# TL1P4.net
KiCad netlist of a schematic drawn in EAGLE
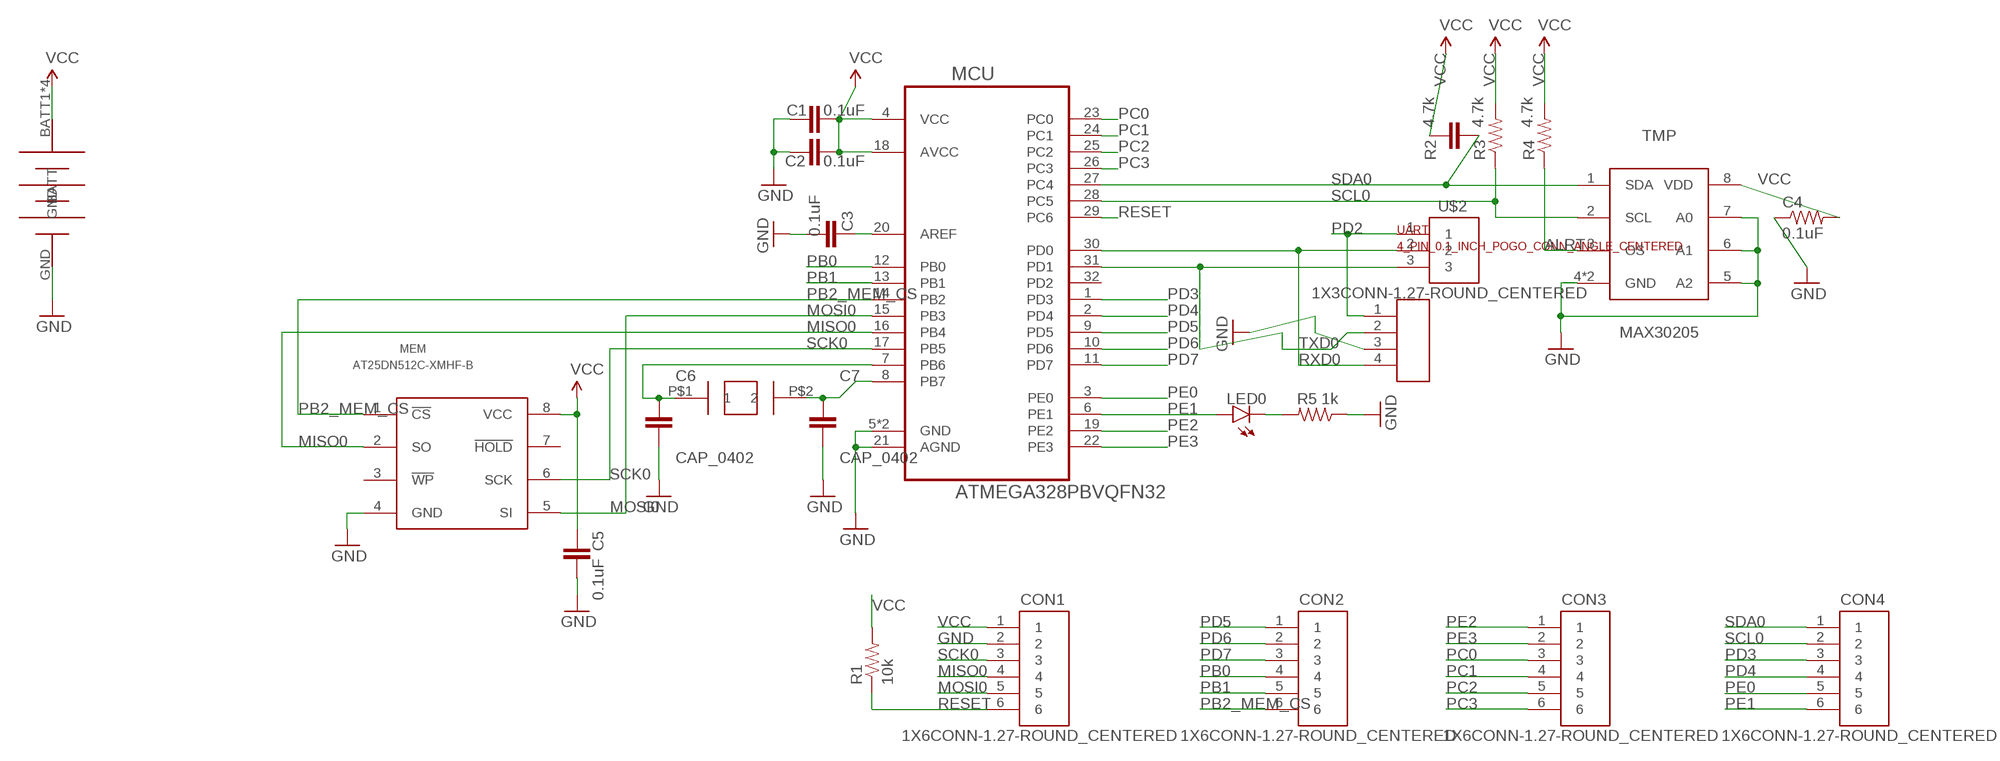
[diagram p0: schematic, sheet 1]

(export (version "E")
  (design (tool "Eeschema 10.0.6"))
  (components
    (comp (ref "C1")
      (value "0.1uF")
      (footprint "eagle-import:RES_CAP_0201")
      (libsource (lib "eagle-import") (part "CAP_0201_CERAMIC"))
    )
    (comp (ref "C2")
      (value "0.1uF")
      (footprint "eagle-import:RES_CAP_0201")
      (libsource (lib "eagle-import") (part "CAP_0201_CERAMIC"))
    )
    (comp (ref "C3")
      (value "0.1uF")
      (footprint "eagle-import:RES_CAP_0201")
      (libsource (lib "eagle-import") (part "CAP_0201_CERAMIC"))
    )
    (comp (ref "C4")
      (value "0.1uF")
      (footprint "eagle-import:RES_CAP_0201")
      (libsource (lib "eagle-import") (part "RES_0201_CERAMIC"))
    )
    (comp (ref "C5")
      (value "0.1uF")
      (footprint "eagle-import:RES_CAP_0201")
      (libsource (lib "eagle-import") (part "CAP_0201_CERAMIC"))
    )
    (comp (ref "C6")
      (value "CAP_0402")
      (footprint "eagle-import:SMD_0402")
      (libsource (lib "eagle-import") (part "CAP_0402"))
    )
    (comp (ref "C7")
      (value "CAP_0402")
      (footprint "eagle-import:SMD_0402")
      (libsource (lib "eagle-import") (part "CAP_0402"))
    )
    (comp (ref "CON1")
      (value "1X6CONN-1.27-ROUND_CENTERED")
      (footprint "eagle-import:1X6_1.27_ROUND_CENTERED")
      (libsource (lib "eagle-import") (part "1X6CONN-1.27-ROUND_CENTERED"))
    )
    (comp (ref "CON2")
      (value "1X6CONN-1.27-ROUND_CENTERED")
      (footprint "eagle-import:1X6_1.27_ROUND_CENTERED")
      (libsource (lib "eagle-import") (part "1X6CONN-1.27-ROUND_CENTERED"))
    )
    (comp (ref "CON3")
      (value "1X6CONN-1.27-ROUND_CENTERED")
      (footprint "eagle-import:1X6_1.27_ROUND_CENTERED")
      (libsource (lib "eagle-import") (part "1X6CONN-1.27-ROUND_CENTERED"))
    )
    (comp (ref "CON4")
      (value "1X6CONN-1.27-ROUND_CENTERED")
      (footprint "eagle-import:1X6_1.27_ROUND_CENTERED")
      (libsource (lib "eagle-import") (part "1X6CONN-1.27-ROUND_CENTERED"))
    )
    (comp (ref "LED0")
      (value "LED_0402")
      (footprint "eagle-import:LED_0402")
      (libsource (lib "eagle-import") (part "LED_0402"))
    )
    (comp (ref "MCU")
      (value "ATMEGA328PBVQFN32")
      (footprint "eagle-import:ATMEGA328PB_VFQFN32")
      (libsource (lib "eagle-import") (part "ATMEGA328PBVQFN32"))
    )
    (comp (ref "MEM")
      (value "AT25DN512C-XMHF-B")
      (footprint "eagle-import:TSSSOP-8")
      (libsource (lib "eagle-import") (part "AT25DN512C-XMHF-B"))
    )
    (comp (ref "R1")
      (value "10k")
      (footprint "eagle-import:RES_CAP_0201")
      (libsource (lib "eagle-import") (part "RES_0201_CERAMIC"))
    )
    (comp (ref "R2")
      (value "4.7k")
      (footprint "eagle-import:RES_CAP_0201")
      (libsource (lib "eagle-import") (part "CAP_0201_CERAMIC"))
    )
    (comp (ref "R3")
      (value "4.7k")
      (footprint "eagle-import:RES_CAP_0201")
      (libsource (lib "eagle-import") (part "RES_0201_CERAMIC"))
    )
    (comp (ref "R4")
      (value "4.7k")
      (footprint "eagle-import:RES_CAP_0201")
      (libsource (lib "eagle-import") (part "RES_0201_CERAMIC"))
    )
    (comp (ref "R5")
      (value "1k")
      (footprint "eagle-import:RES_CAP_0201")
      (libsource (lib "eagle-import") (part "RES_0201_CERAMIC"))
    )
    (comp (ref "T1")
      (value "ABS07AIG")
      (footprint "eagle-import:ABS07AIG")
      (libsource (lib "eagle-import") (part "ABS07AIG"))
    )
    (comp (ref "TMP")
      (value "MAX30205")
      (footprint "eagle-import:MAX30205_TDFN8")
      (libsource (lib "eagle-import") (part "MAX30205"))
    )
    (comp (ref "U$1")
      (value "LINX-CR2032-BAT-HLD-THM")
      (footprint "eagle-import:CR2032-LINX-THM")
      (libsource (lib "eagle-import") (part "LINX-CR2032-BAT-HLD-THM"))
    )
    (comp (ref "U$2")
      (value "1X3CONN-1.27-ROUND_CENTERED")
      (footprint "eagle-import:1X3_1.27_ROUND_CENTERED")
      (libsource (lib "eagle-import") (part "1X3CONN-1.27-ROUND_CENTERED"))
    )
    (comp (ref "UART")
      (value "4_PIN_0.1_INCH_POGO_CONN_ANGLE_CENTERED")
      (footprint "eagle-import:4_PIN_0.1__POGO_ANGLE_CENTERED")
      (libsource (lib "eagle-import") (part "4_PIN_0.1_INCH_POGO_CONN_ANGLE_CENTERED"))
    )
  )
  (nets
    (net (code "1") (name "/ALRT") (class "Default")
      (node (ref "R4") (pin "2") (pinfunction "2_2") (pintype "passive"))
      (node (ref "TMP") (pin "3") (pinfunction "OS_3") (pintype "bidirectional"))
    )
    (net (code "2") (name "/MISO0") (class "Default")
      (node (ref "CON1") (pin "4") (pinfunction "4_4") (pintype "bidirectional"))
      (node (ref "MCU") (pin "16") (pinfunction "PB4_16") (pintype "bidirectional"))
      (node (ref "MEM") (pin "2") (pinfunction "SO_2") (pintype "bidirectional"))
    )
    (net (code "3") (name "/MOSI0") (class "Default")
      (node (ref "CON1") (pin "5") (pinfunction "5_5") (pintype "bidirectional"))
      (node (ref "MCU") (pin "15") (pinfunction "PB3_15") (pintype "bidirectional"))
      (node (ref "MEM") (pin "5") (pinfunction "SI_5") (pintype "bidirectional"))
    )
    (net (code "4") (name "/PB0") (class "Default")
      (node (ref "CON2") (pin "4") (pinfunction "4_4") (pintype "bidirectional"))
      (node (ref "MCU") (pin "12") (pinfunction "PB0_12") (pintype "bidirectional"))
    )
    (net (code "5") (name "/PB1") (class "Default")
      (node (ref "CON2") (pin "5") (pinfunction "5_5") (pintype "bidirectional"))
      (node (ref "MCU") (pin "13") (pinfunction "PB1_13") (pintype "bidirectional"))
    )
    (net (code "6") (name "/PB2_MEM_CS") (class "Default")
      (node (ref "CON2") (pin "6") (pinfunction "6_6") (pintype "bidirectional"))
      (node (ref "MCU") (pin "14") (pinfunction "PB2_14") (pintype "bidirectional"))
      (node (ref "MEM") (pin "1") (pinfunction "~{CS}_1") (pintype "bidirectional"))
    )
    (net (code "7") (name "/PC0") (class "Default")
      (node (ref "CON3") (pin "3") (pinfunction "3_3") (pintype "bidirectional"))
      (node (ref "MCU") (pin "23") (pinfunction "PC0_23") (pintype "bidirectional"))
    )
    (net (code "8") (name "/PC1") (class "Default")
      (node (ref "CON3") (pin "4") (pinfunction "4_4") (pintype "bidirectional"))
      (node (ref "MCU") (pin "24") (pinfunction "PC1_24") (pintype "bidirectional"))
    )
    (net (code "9") (name "/PC2") (class "Default")
      (node (ref "CON3") (pin "5") (pinfunction "5_5") (pintype "bidirectional"))
      (node (ref "MCU") (pin "25") (pinfunction "PC2_25") (pintype "bidirectional"))
    )
    (net (code "10") (name "/PC3") (class "Default")
      (node (ref "CON3") (pin "6") (pinfunction "6_6") (pintype "bidirectional"))
      (node (ref "MCU") (pin "26") (pinfunction "PC3_26") (pintype "bidirectional"))
    )
    (net (code "11") (name "/PD2") (class "Default")
      (node (ref "U$2") (pin "1") (pinfunction "1_1") (pintype "bidirectional"))
      (node (ref "UART") (pin "1") (pinfunction "1_1") (pintype "bidirectional"))
    )
    (net (code "12") (name "/PD3") (class "Default")
      (node (ref "CON4") (pin "3") (pinfunction "3_3") (pintype "bidirectional"))
      (node (ref "MCU") (pin "1") (pinfunction "PD3_1") (pintype "bidirectional"))
    )
    (net (code "13") (name "/PD4") (class "Default")
      (node (ref "CON4") (pin "4") (pinfunction "4_4") (pintype "bidirectional"))
      (node (ref "MCU") (pin "2") (pinfunction "PD4_2") (pintype "bidirectional"))
    )
    (net (code "14") (name "/PD5") (class "Default")
      (node (ref "CON2") (pin "1") (pinfunction "1_1") (pintype "bidirectional"))
      (node (ref "MCU") (pin "9") (pinfunction "PD5_9") (pintype "bidirectional"))
    )
    (net (code "15") (name "/PD6") (class "Default")
      (node (ref "CON2") (pin "2") (pinfunction "2_2") (pintype "bidirectional"))
      (node (ref "MCU") (pin "10") (pinfunction "PD6_10") (pintype "bidirectional"))
    )
    (net (code "16") (name "/PD7") (class "Default")
      (node (ref "CON2") (pin "3") (pinfunction "3_3") (pintype "bidirectional"))
      (node (ref "MCU") (pin "11") (pinfunction "PD7_11") (pintype "bidirectional"))
    )
    (net (code "17") (name "/PE0") (class "Default")
      (node (ref "CON4") (pin "5") (pinfunction "5_5") (pintype "bidirectional"))
      (node (ref "MCU") (pin "3") (pinfunction "PE0_3") (pintype "bidirectional"))
    )
    (net (code "18") (name "/PE1") (class "Default")
      (node (ref "CON4") (pin "6") (pinfunction "6_6") (pintype "bidirectional"))
      (node (ref "LED0") (pin "ANODE") (pinfunction "A_ANODE") (pintype "passive"))
      (node (ref "MCU") (pin "6") (pinfunction "PE1_6") (pintype "bidirectional"))
    )
    (net (code "19") (name "/PE2") (class "Default")
      (node (ref "CON3") (pin "1") (pinfunction "1_1") (pintype "bidirectional"))
      (node (ref "MCU") (pin "19") (pinfunction "PE2_19") (pintype "bidirectional"))
    )
    (net (code "20") (name "/PE3") (class "Default")
      (node (ref "CON3") (pin "2") (pinfunction "2_2") (pintype "bidirectional"))
      (node (ref "MCU") (pin "22") (pinfunction "PE3_22") (pintype "bidirectional"))
    )
    (net (code "21") (name "/RESET") (class "Default")
      (node (ref "CON1") (pin "6") (pinfunction "6_6") (pintype "bidirectional"))
      (node (ref "MCU") (pin "29") (pinfunction "PC6_29") (pintype "bidirectional"))
      (node (ref "R1") (pin "2") (pinfunction "2_2") (pintype "passive"))
    )
    (net (code "22") (name "/RXD0") (class "Default")
      (node (ref "MCU") (pin "30") (pinfunction "PD0_30") (pintype "bidirectional"))
      (node (ref "U$2") (pin "2") (pinfunction "2_2") (pintype "bidirectional"))
      (node (ref "UART") (pin "4") (pinfunction "4_4") (pintype "bidirectional"))
    )
    (net (code "23") (name "/SCK0") (class "Default")
      (node (ref "CON1") (pin "3") (pinfunction "3_3") (pintype "bidirectional"))
      (node (ref "MCU") (pin "17") (pinfunction "PB5_17") (pintype "bidirectional"))
      (node (ref "MEM") (pin "6") (pinfunction "SCK_6") (pintype "bidirectional"))
    )
    (net (code "24") (name "/SCL0") (class "Default")
      (node (ref "CON4") (pin "2") (pinfunction "2_2") (pintype "bidirectional"))
      (node (ref "MCU") (pin "28") (pinfunction "PC5_28") (pintype "bidirectional"))
      (node (ref "R3") (pin "2") (pinfunction "2_2") (pintype "passive"))
      (node (ref "TMP") (pin "2") (pinfunction "SCL_2") (pintype "bidirectional"))
    )
    (net (code "25") (name "/SDA0") (class "Default")
      (node (ref "CON4") (pin "1") (pinfunction "1_1") (pintype "bidirectional"))
      (node (ref "MCU") (pin "27") (pinfunction "PC4_27") (pintype "bidirectional"))
      (node (ref "R2") (pin "2") (pinfunction "2_2") (pintype "passive"))
      (node (ref "TMP") (pin "1") (pinfunction "SDA_1") (pintype "bidirectional"))
    )
    (net (code "26") (name "/TXD0") (class "Default")
      (node (ref "MCU") (pin "31") (pinfunction "PD1_31") (pintype "bidirectional"))
      (node (ref "U$2") (pin "3") (pinfunction "3_3") (pintype "bidirectional"))
      (node (ref "UART") (pin "2") (pinfunction "2_2") (pintype "bidirectional"))
    )
    (net (code "27") (name "GND") (class "Default")
      (node (ref "C1") (pin "2") (pinfunction "2_2") (pintype "passive"))
      (node (ref "C2") (pin "2") (pinfunction "2_2") (pintype "passive"))
      (node (ref "C3") (pin "2") (pinfunction "2_2") (pintype "passive"))
      (node (ref "C4") (pin "2") (pinfunction "2_2") (pintype "passive"))
      (node (ref "C5") (pin "2") (pinfunction "2_2") (pintype "passive"))
      (node (ref "C6") (pin "2") (pinfunction "2_2") (pintype "bidirectional"))
      (node (ref "C7") (pin "2") (pinfunction "2_2") (pintype "bidirectional"))
      (node (ref "CON1") (pin "2") (pinfunction "2_2") (pintype "bidirectional"))
      (node (ref "MCU") (pin "21") (pinfunction "AGND_21") (pintype "passive"))
      (node (ref "MCU") (pin "5") (pinfunction "GND_5") (pintype "passive"))
      (node (ref "MCU") (pin "PAD") (pinfunction "GND_PAD") (pintype "passive"))
      (node (ref "MEM") (pin "4") (pinfunction "GND_4") (pintype "bidirectional"))
      (node (ref "R5") (pin "2") (pinfunction "2_2") (pintype "passive"))
      (node (ref "TMP") (pin "4") (pinfunction "GND_4") (pintype "bidirectional"))
      (node (ref "TMP") (pin "5") (pinfunction "A2_5") (pintype "bidirectional"))
      (node (ref "TMP") (pin "6") (pinfunction "A1_6") (pintype "bidirectional"))
      (node (ref "TMP") (pin "7") (pinfunction "A0_7") (pintype "bidirectional"))
      (node (ref "TMP") (pin "PAD") (pinfunction "GND_PAD") (pintype "bidirectional"))
      (node (ref "U$1") (pin "GND") (pinfunction "GND_GND") (pintype "bidirectional"))
      (node (ref "UART") (pin "3") (pinfunction "3_3") (pintype "bidirectional"))
    )
    (net (code "28") (name "Net-(LED0-C)") (class "Default")
      (node (ref "LED0") (pin "CATHODE") (pinfunction "C_CATHODE") (pintype "passive"))
      (node (ref "R5") (pin "1") (pinfunction "1_1") (pintype "passive"))
    )
    (net (code "29") (name "Net-(MCU-AREF)") (class "Default")
      (node (ref "C3") (pin "1") (pinfunction "1_1") (pintype "passive"))
      (node (ref "MCU") (pin "20") (pinfunction "AREF_20") (pintype "input"))
    )
    (net (code "30") (name "Net-(MCU-PB6)") (class "Default")
      (node (ref "C6") (pin "1") (pinfunction "1_1") (pintype "bidirectional"))
      (node (ref "MCU") (pin "7") (pinfunction "PB6_7") (pintype "bidirectional"))
      (node (ref "T1") (pin "P$1") (pinfunction "1_P$1") (pintype "bidirectional"))
    )
    (net (code "31") (name "Net-(MCU-PB7)") (class "Default")
      (node (ref "C7") (pin "1") (pinfunction "1_1") (pintype "bidirectional"))
      (node (ref "MCU") (pin "8") (pinfunction "PB7_8") (pintype "bidirectional"))
      (node (ref "T1") (pin "P$2") (pinfunction "2_P$2") (pintype "bidirectional"))
    )
    (net (code "32") (name "VCC") (class "Default")
      (node (ref "C1") (pin "1") (pinfunction "1_1") (pintype "passive"))
      (node (ref "C2") (pin "1") (pinfunction "1_1") (pintype "passive"))
      (node (ref "C4") (pin "1") (pinfunction "1_1") (pintype "passive"))
      (node (ref "C5") (pin "1") (pinfunction "1_1") (pintype "passive"))
      (node (ref "CON1") (pin "1") (pinfunction "1_1") (pintype "bidirectional"))
      (node (ref "MCU") (pin "18") (pinfunction "AVCC_18") (pintype "power_in"))
      (node (ref "MCU") (pin "4") (pinfunction "VCC_4") (pintype "power_in"))
      (node (ref "MEM") (pin "8") (pinfunction "VCC_8") (pintype "bidirectional"))
      (node (ref "R1") (pin "1") (pinfunction "1_1") (pintype "passive"))
      (node (ref "R2") (pin "1") (pinfunction "1_1") (pintype "passive"))
      (node (ref "R3") (pin "1") (pinfunction "1_1") (pintype "passive"))
      (node (ref "R4") (pin "1") (pinfunction "1_1") (pintype "passive"))
      (node (ref "TMP") (pin "8") (pinfunction "VDD_8") (pintype "bidirectional"))
      (node (ref "U$1") (pin "BATT1") (pinfunction "BATT_BATT1") (pintype "bidirectional"))
      (node (ref "U$1") (pin "BATT2") (pinfunction "BATT_BATT2") (pintype "bidirectional"))
      (node (ref "U$1") (pin "BATT3") (pinfunction "BATT_BATT3") (pintype "bidirectional"))
      (node (ref "U$1") (pin "BATT4") (pinfunction "BATT_BATT4") (pintype "bidirectional"))
    )
    (net (code "33") (name "unconnected-(MCU-PD2-Pad32)") (class "Default")
      (node (ref "MCU") (pin "32") (pinfunction "PD2_32") (pintype "bidirectional"))
    )
    (net (code "34") (name "unconnected-(MEM-~{HOLD}-Pad7)") (class "Default")
      (node (ref "MEM") (pin "7") (pinfunction "~{HOLD}_7") (pintype "bidirectional"))
    )
    (net (code "35") (name "unconnected-(MEM-~{WP}-Pad3)") (class "Default")
      (node (ref "MEM") (pin "3") (pinfunction "~{WP}_3") (pintype "bidirectional"))
    )
  )
)
